# Adapter.net
KiCad netlist of a schematic drawn in Altium Designer
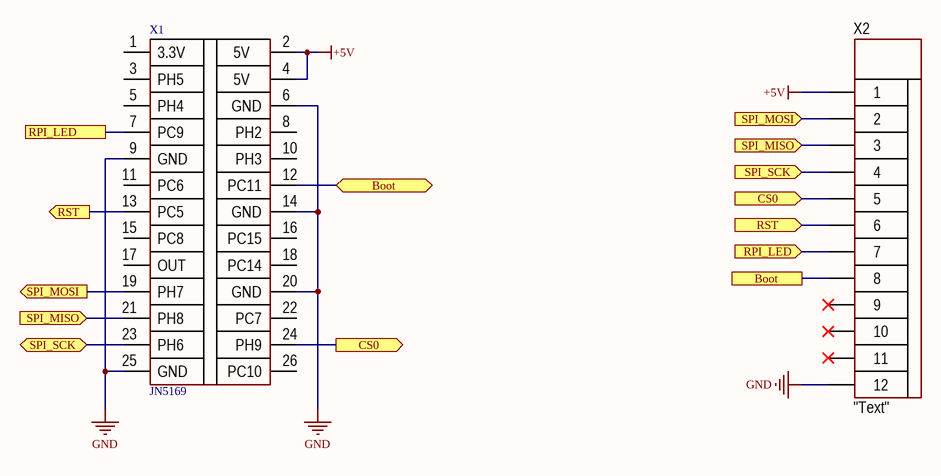
[diagram p0: Adapter.SchDoc]

(export (version "E")
  (design (tool "Eeschema 10.0.6"))
  (components
    (comp (ref "X1")
      (value "JN5169")
      (footprint "MOD: Orange pi zero 2 (26pin only) mirror cut")
      (libsource (lib "General_Library") (part "OrangePi Zero 2(26pin only)"))
    )
    (comp (ref "X2")
      (value "~")
      (footprint "CON: 0526101233")
      (fields
        (field (name "MANUFACTURER") "Connfly")
        (field (name "VALUEMANUFACTURERPARTNUMBER") ", 20pin, 2.54mm, 500VAC, 3A")
        (field (name "PARTNUMBER") "PLS-20")
        (field (name "COMMENTTEXT") "\"Text\"")
      )
      (libsource (lib "General_Library") (part "CON{colon} 12 Pin V1"))
    )
  )
  (nets
    (net (code "1") (name "+5V") (class "Default")
      (node (ref "X1") (pin "2") (pinfunction "5V_2") (pintype "passive"))
      (node (ref "X1") (pin "4") (pinfunction "5V_4") (pintype "passive"))
      (node (ref "X2") (pin "1") (pinfunction "1_1") (pintype "passive"))
    )
    (net (code "2") (name "/Boot") (class "Default")
      (node (ref "X1") (pin "12") (pinfunction "PC11_12") (pintype "passive"))
      (node (ref "X2") (pin "8") (pinfunction "8_8") (pintype "passive"))
    )
    (net (code "3") (name "/CS0") (class "Default")
      (node (ref "X1") (pin "24") (pinfunction "PH9_24") (pintype "passive"))
      (node (ref "X2") (pin "5") (pinfunction "5_5") (pintype "passive"))
    )
    (net (code "4") (name "/RPI_LED") (class "Default")
      (node (ref "X1") (pin "7") (pinfunction "PC9_7") (pintype "passive"))
      (node (ref "X2") (pin "7") (pinfunction "7_7") (pintype "passive"))
    )
    (net (code "5") (name "/RST") (class "Default")
      (node (ref "X1") (pin "13") (pinfunction "PC5_13") (pintype "passive"))
      (node (ref "X2") (pin "6") (pinfunction "6_6") (pintype "passive"))
    )
    (net (code "6") (name "/SPI_MISO") (class "Default")
      (node (ref "X1") (pin "21") (pinfunction "PH8_21") (pintype "passive"))
      (node (ref "X2") (pin "3") (pinfunction "3_3") (pintype "passive"))
    )
    (net (code "7") (name "/SPI_MOSI") (class "Default")
      (node (ref "X1") (pin "19") (pinfunction "PH7_19") (pintype "passive"))
      (node (ref "X2") (pin "2") (pinfunction "2_2") (pintype "passive"))
    )
    (net (code "8") (name "/SPI_SCK") (class "Default")
      (node (ref "X1") (pin "23") (pinfunction "PH6_23") (pintype "passive"))
      (node (ref "X2") (pin "4") (pinfunction "4_4") (pintype "passive"))
    )
    (net (code "9") (name "GND") (class "Default")
      (node (ref "X1") (pin "14") (pinfunction "GND_14") (pintype "passive"))
      (node (ref "X1") (pin "20") (pinfunction "GND_20") (pintype "passive"))
      (node (ref "X1") (pin "25") (pinfunction "GND_25") (pintype "passive"))
      (node (ref "X1") (pin "6") (pinfunction "GND_6") (pintype "passive"))
      (node (ref "X1") (pin "9") (pinfunction "GND_9") (pintype "passive"))
      (node (ref "X2") (pin "12") (pinfunction "12_12") (pintype "passive"))
    )
    (net (code "10") (name "unconnected-(X1-3.3V-Pad1)") (class "Default")
      (node (ref "X1") (pin "1") (pinfunction "3.3V_1") (pintype "passive"))
    )
    (net (code "11") (name "unconnected-(X1-OUT-Pad17)") (class "Default")
      (node (ref "X1") (pin "17") (pinfunction "OUT_17") (pintype "passive"))
    )
    (net (code "12") (name "unconnected-(X1-PC6-Pad11)") (class "Default")
      (node (ref "X1") (pin "11") (pinfunction "PC6_11") (pintype "passive"))
    )
    (net (code "13") (name "unconnected-(X1-PC7-Pad22)") (class "Default")
      (node (ref "X1") (pin "22") (pinfunction "PC7_22") (pintype "passive"))
    )
    (net (code "14") (name "unconnected-(X1-PC8-Pad15)") (class "Default")
      (node (ref "X1") (pin "15") (pinfunction "PC8_15") (pintype "passive"))
    )
    (net (code "15") (name "unconnected-(X1-PC10-Pad26)") (class "Default")
      (node (ref "X1") (pin "26") (pinfunction "PC10_26") (pintype "passive"))
    )
    (net (code "16") (name "unconnected-(X1-PC14-Pad18)") (class "Default")
      (node (ref "X1") (pin "18") (pinfunction "PC14_18") (pintype "passive"))
    )
    (net (code "17") (name "unconnected-(X1-PC15-Pad16)") (class "Default")
      (node (ref "X1") (pin "16") (pinfunction "PC15_16") (pintype "passive"))
    )
    (net (code "18") (name "unconnected-(X1-PH2-Pad8)") (class "Default")
      (node (ref "X1") (pin "8") (pinfunction "PH2_8") (pintype "passive"))
    )
    (net (code "19") (name "unconnected-(X1-PH3-Pad10)") (class "Default")
      (node (ref "X1") (pin "10") (pinfunction "PH3_10") (pintype "passive"))
    )
    (net (code "20") (name "unconnected-(X1-PH4-Pad5)") (class "Default")
      (node (ref "X1") (pin "5") (pinfunction "PH4_5") (pintype "passive"))
    )
    (net (code "21") (name "unconnected-(X1-PH5-Pad3)") (class "Default")
      (node (ref "X1") (pin "3") (pinfunction "PH5_3") (pintype "passive"))
    )
    (net (code "22") (name "unconnected-(X2-Pad9)") (class "Default")
      (node (ref "X2") (pin "9") (pinfunction "9_9") (pintype "passive+no_connect"))
    )
    (net (code "23") (name "unconnected-(X2-Pad10)") (class "Default")
      (node (ref "X2") (pin "10") (pinfunction "10_10") (pintype "passive+no_connect"))
    )
    (net (code "24") (name "unconnected-(X2-Pad11)") (class "Default")
      (node (ref "X2") (pin "11") (pinfunction "11_11") (pintype "passive+no_connect"))
    )
  )
)
